# MicroFM.net
KiCad netlist of a schematic drawn in Altium Designer
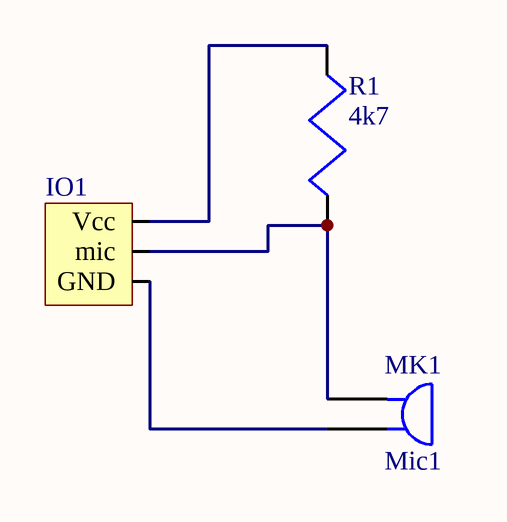
[diagram p0: MicroFM.SchDoc]

(export (version "E")
  (design (tool "Eeschema 10.0.6"))
  (components
    (comp (ref "IO1") (value "MicroIO") (footprint "MicroIO3x1") (libsource (lib "epf") (part "MicroIO")))
    (comp (ref "MK1")
      (value "Mic1")
      (footprint "Mic1")
      (description "Microphone")
      (fields (field (name "PUBLISHER") "Altium Limited"))
      (libsource (lib "Miscellaneous Devices") (part "Mic1"))
    )
    (comp (ref "R1")
      (value "4k7")
      (footprint "proto-resistor")
      (description "Resistencia con conector de prototipado")
      (libsource (lib "cia-opa") (part "proto-resistor"))
    )
  )
  (nets
    (net (code "1") (name "Net-(IO1-GND)") (class "Default")
      (node (ref "IO1") (pin "2") (pinfunction "GND_2") (pintype "passive"))
      (node (ref "MK1") (pin "2") (pinfunction "2_2") (pintype "passive"))
    )
    (net (code "2") (name "Net-(IO1-Vcc)") (class "Default")
      (node (ref "IO1") (pin "0") (pinfunction "Vcc_0") (pintype "passive"))
      (node (ref "R1") (pin "1") (pinfunction "1_1") (pintype "passive"))
    )
    (net (code "3") (name "Net-(IO1-mic)") (class "Default")
      (node (ref "IO1") (pin "1") (pinfunction "mic_1") (pintype "passive"))
      (node (ref "MK1") (pin "1") (pinfunction "1_1") (pintype "passive"))
      (node (ref "R1") (pin "2") (pinfunction "2_2") (pintype "passive"))
    )
  )
)
